# 51.net
KiCad netlist of a schematic drawn in Altium Designer
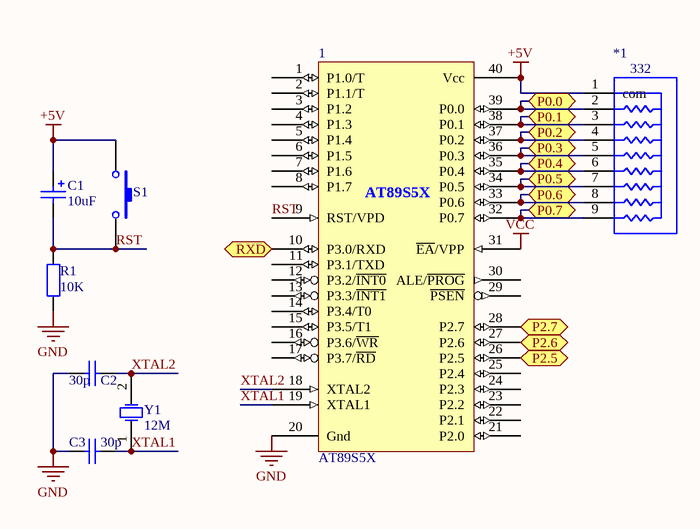
[diagram p0: 51 最小系统.SchDoc]

(export (version "E")
  (design (tool "Eeschema 10.0.6"))
  (components
    (comp (ref "*1") (value "排阻 DIP-9") (footprint "HDR1X9") (libsource (lib "自制库（原理图文件）") (part "排阻 DIP-9")))
    (comp (ref "1") (value "AT89S5X") (footprint "DIP-40") (libsource (lib "自制库（原理图文件）") (part "AT89S5X")))
    (comp (ref "C1")
      (value "电解电容")
      (footprint "电解电容")
      (fields (field (name "ALTIUM_UNNAMED_1") "10uF"))
      (libsource (lib "自制库（原理图文件）") (part "电解电容"))
    )
    (comp (ref "C2")
      (value "瓷片电容")
      (footprint "瓷片电容")
      (fields (field (name "ALTIUM_UNNAMED_1") "30p"))
      (libsource (lib "自制库（原理图文件）") (part "瓷片电容"))
    )
    (comp (ref "C3")
      (value "瓷片电容")
      (footprint "瓷片电容")
      (fields (field (name "ALTIUM_UNNAMED_1") "30p"))
      (libsource (lib "自制库（原理图文件）") (part "瓷片电容"))
    )
    (comp (ref "R1")
      (value "10K")
      (footprint "AXIAL-0.4")
      (description "Resistor")
      (fields (field (name "Comment") "Res2") (field (name "PUBLISHER") "Altium Limited"))
      (libsource (lib "Miscellaneous Devices") (part "Res2"))
    )
    (comp (ref "S1")
      (value "SW-PB")
      (footprint "SPST-2")
      (description "Switch")
      (fields (field (name "PUBLISHER") "Altium Limited"))
      (libsource (lib "Miscellaneous Devices") (part "SW-PB"))
    )
    (comp (ref "Y1")
      (value "12M")
      (footprint "R38")
      (description "Crystal Oscillator")
      (fields (field (name "PUBLISHER") "Altium Limited"))
      (libsource (lib "Miscellaneous Devices") (part "XTAL"))
    )
  )
  (nets
    (net (code "1") (name "+5V") (class "Default")
      (node (ref "*1") (pin "1") (pinfunction "com_1") (pintype "passive"))
      (node (ref "1") (pin "40") (pinfunction "Vcc_40") (pintype "power_in"))
      (node (ref "C1") (pin "1") (pinfunction "1_1") (pintype "passive"))
      (node (ref "S1") (pin "1") (pinfunction "1_1") (pintype "passive"))
    )
    (net (code "2") (name "/P0.0") (class "Default")
      (node (ref "*1") (pin "2") (pinfunction "1_2") (pintype "passive"))
      (node (ref "1") (pin "39") (pinfunction "P0.0_39") (pintype "bidirectional"))
    )
    (net (code "3") (name "/P0.1") (class "Default")
      (node (ref "*1") (pin "3") (pinfunction "2_3") (pintype "passive"))
      (node (ref "1") (pin "38") (pinfunction "P0.1_38") (pintype "bidirectional"))
    )
    (net (code "4") (name "/P0.2") (class "Default")
      (node (ref "*1") (pin "4") (pinfunction "3_4") (pintype "passive"))
      (node (ref "1") (pin "37") (pinfunction "P0.2_37") (pintype "bidirectional"))
    )
    (net (code "5") (name "/P0.3") (class "Default")
      (node (ref "*1") (pin "5") (pinfunction "4_5") (pintype "passive"))
      (node (ref "1") (pin "36") (pinfunction "P0.3_36") (pintype "bidirectional"))
    )
    (net (code "6") (name "/P0.4") (class "Default")
      (node (ref "*1") (pin "6") (pinfunction "5_6") (pintype "passive"))
      (node (ref "1") (pin "35") (pinfunction "P0.4_35") (pintype "bidirectional"))
    )
    (net (code "7") (name "/P0.5") (class "Default")
      (node (ref "*1") (pin "7") (pinfunction "6_7") (pintype "passive"))
      (node (ref "1") (pin "34") (pinfunction "P0.5_34") (pintype "bidirectional"))
    )
    (net (code "8") (name "/P0.6") (class "Default")
      (node (ref "*1") (pin "8") (pinfunction "7_8") (pintype "passive"))
      (node (ref "1") (pin "33") (pinfunction "P0.6_33") (pintype "bidirectional"))
    )
    (net (code "9") (name "/P0.7") (class "Default")
      (node (ref "*1") (pin "9") (pinfunction "8_9") (pintype "passive"))
      (node (ref "1") (pin "32") (pinfunction "P0.7_32") (pintype "bidirectional"))
    )
    (net (code "10") (name "/P2.5") (class "Default")
      (node (ref "1") (pin "26") (pinfunction "P2.5_26") (pintype "bidirectional"))
    )
    (net (code "11") (name "/P2.6") (class "Default")
      (node (ref "1") (pin "27") (pinfunction "P2.6_27") (pintype "bidirectional"))
    )
    (net (code "12") (name "/P2.7") (class "Default")
      (node (ref "1") (pin "28") (pinfunction "P2.7_28") (pintype "bidirectional"))
    )
    (net (code "13") (name "/RST") (class "Default")
      (node (ref "1") (pin "9") (pinfunction "RST/VPD_9") (pintype "input"))
      (node (ref "C1") (pin "2") (pinfunction "2_2") (pintype "passive"))
      (node (ref "R1") (pin "2") (pinfunction "2_2") (pintype "passive"))
      (node (ref "S1") (pin "2") (pinfunction "2_2") (pintype "passive"))
    )
    (net (code "14") (name "/RXD") (class "Default")
      (node (ref "1") (pin "10") (pinfunction "P3.0/RXD_10") (pintype "bidirectional"))
    )
    (net (code "15") (name "/XTAL1") (class "Default")
      (node (ref "1") (pin "19") (pinfunction "XTAL1_19") (pintype "input"))
      (node (ref "C3") (pin "2") (pinfunction "2_2") (pintype "passive"))
      (node (ref "Y1") (pin "1") (pinfunction "OSC1_1") (pintype "passive"))
    )
    (net (code "16") (name "/XTAL2") (class "Default")
      (node (ref "1") (pin "18") (pinfunction "XTAL2_18") (pintype "input"))
      (node (ref "C2") (pin "2") (pinfunction "2_2") (pintype "passive"))
      (node (ref "Y1") (pin "2") (pinfunction "OSC2_2") (pintype "passive"))
    )
    (net (code "17") (name "GND") (class "Default")
      (node (ref "1") (pin "20") (pinfunction "Gnd_20") (pintype "power_in"))
      (node (ref "C2") (pin "1") (pinfunction "1_1") (pintype "passive"))
      (node (ref "C3") (pin "1") (pinfunction "1_1") (pintype "passive"))
      (node (ref "R1") (pin "1") (pinfunction "1_1") (pintype "passive"))
    )
    (net (code "18") (name "VCC") (class "Default")
      (node (ref "1") (pin "31") (pinfunction "~{EA}/VPP_31") (pintype "input"))
    )
    (net (code "19") (name "unconnected-(1-ALE{slash}~{PROG}-Pad30)") (class "Default")
      (node (ref "1") (pin "30") (pinfunction "ALE/~{PROG}_30") (pintype "output"))
    )
    (net (code "20") (name "unconnected-(1-P1.0{slash}T-Pad1)") (class "Default")
      (node (ref "1") (pin "1") (pinfunction "P1.0/T_1") (pintype "bidirectional"))
    )
    (net (code "21") (name "unconnected-(1-P1.1{slash}T-Pad2)") (class "Default")
      (node (ref "1") (pin "2") (pinfunction "P1.1/T_2") (pintype "bidirectional"))
    )
    (net (code "22") (name "unconnected-(1-P1.2-Pad3)") (class "Default")
      (node (ref "1") (pin "3") (pinfunction "P1.2_3") (pintype "bidirectional"))
    )
    (net (code "23") (name "unconnected-(1-P1.3-Pad4)") (class "Default")
      (node (ref "1") (pin "4") (pinfunction "P1.3_4") (pintype "bidirectional"))
    )
    (net (code "24") (name "unconnected-(1-P1.4-Pad5)") (class "Default")
      (node (ref "1") (pin "5") (pinfunction "P1.4_5") (pintype "bidirectional"))
    )
    (net (code "25") (name "unconnected-(1-P1.5-Pad6)") (class "Default")
      (node (ref "1") (pin "6") (pinfunction "P1.5_6") (pintype "bidirectional"))
    )
    (net (code "26") (name "unconnected-(1-P1.6-Pad7)") (class "Default")
      (node (ref "1") (pin "7") (pinfunction "P1.6_7") (pintype "bidirectional"))
    )
    (net (code "27") (name "unconnected-(1-P1.7-Pad8)") (class "Default")
      (node (ref "1") (pin "8") (pinfunction "P1.7_8") (pintype "bidirectional"))
    )
    (net (code "28") (name "unconnected-(1-P2.0-Pad21)") (class "Default")
      (node (ref "1") (pin "21") (pinfunction "P2.0_21") (pintype "bidirectional"))
    )
    (net (code "29") (name "unconnected-(1-P2.1-Pad22)") (class "Default")
      (node (ref "1") (pin "22") (pinfunction "P2.1_22") (pintype "bidirectional"))
    )
    (net (code "30") (name "unconnected-(1-P2.2-Pad23)") (class "Default")
      (node (ref "1") (pin "23") (pinfunction "P2.2_23") (pintype "bidirectional"))
    )
    (net (code "31") (name "unconnected-(1-P2.3-Pad24)") (class "Default")
      (node (ref "1") (pin "24") (pinfunction "P2.3_24") (pintype "bidirectional"))
    )
    (net (code "32") (name "unconnected-(1-P2.4-Pad25)") (class "Default")
      (node (ref "1") (pin "25") (pinfunction "P2.4_25") (pintype "bidirectional"))
    )
    (net (code "33") (name "unconnected-(1-P3.1{slash}TXD-Pad11)") (class "Default")
      (node (ref "1") (pin "11") (pinfunction "P3.1/TXD_11") (pintype "bidirectional"))
    )
    (net (code "34") (name "unconnected-(1-P3.2{slash}~{INT0}-Pad12)") (class "Default")
      (node (ref "1") (pin "12") (pinfunction "P3.2/~{INT0}_12") (pintype "bidirectional"))
    )
    (net (code "35") (name "unconnected-(1-P3.3{slash}~{INT1}-Pad13)") (class "Default")
      (node (ref "1") (pin "13") (pinfunction "P3.3/~{INT1}_13") (pintype "bidirectional"))
    )
    (net (code "36") (name "unconnected-(1-P3.4{slash}T0-Pad14)") (class "Default")
      (node (ref "1") (pin "14") (pinfunction "P3.4/T0_14") (pintype "bidirectional"))
    )
    (net (code "37") (name "unconnected-(1-P3.5{slash}T1-Pad15)") (class "Default")
      (node (ref "1") (pin "15") (pinfunction "P3.5/T1_15") (pintype "bidirectional"))
    )
    (net (code "38") (name "unconnected-(1-P3.6{slash}~{WR}-Pad16)") (class "Default")
      (node (ref "1") (pin "16") (pinfunction "P3.6/~{WR}_16") (pintype "bidirectional"))
    )
    (net (code "39") (name "unconnected-(1-P3.7{slash}~{RD}-Pad17)") (class "Default")
      (node (ref "1") (pin "17") (pinfunction "P3.7/~{RD}_17") (pintype "bidirectional"))
    )
    (net (code "40") (name "unconnected-(1-~{PSEN}-Pad29)") (class "Default")
      (node (ref "1") (pin "29") (pinfunction "~{PSEN}_29") (pintype "output"))
    )
  )
)
